# xpoint.net
KiCad netlist of a schematic drawn in Altium Designer
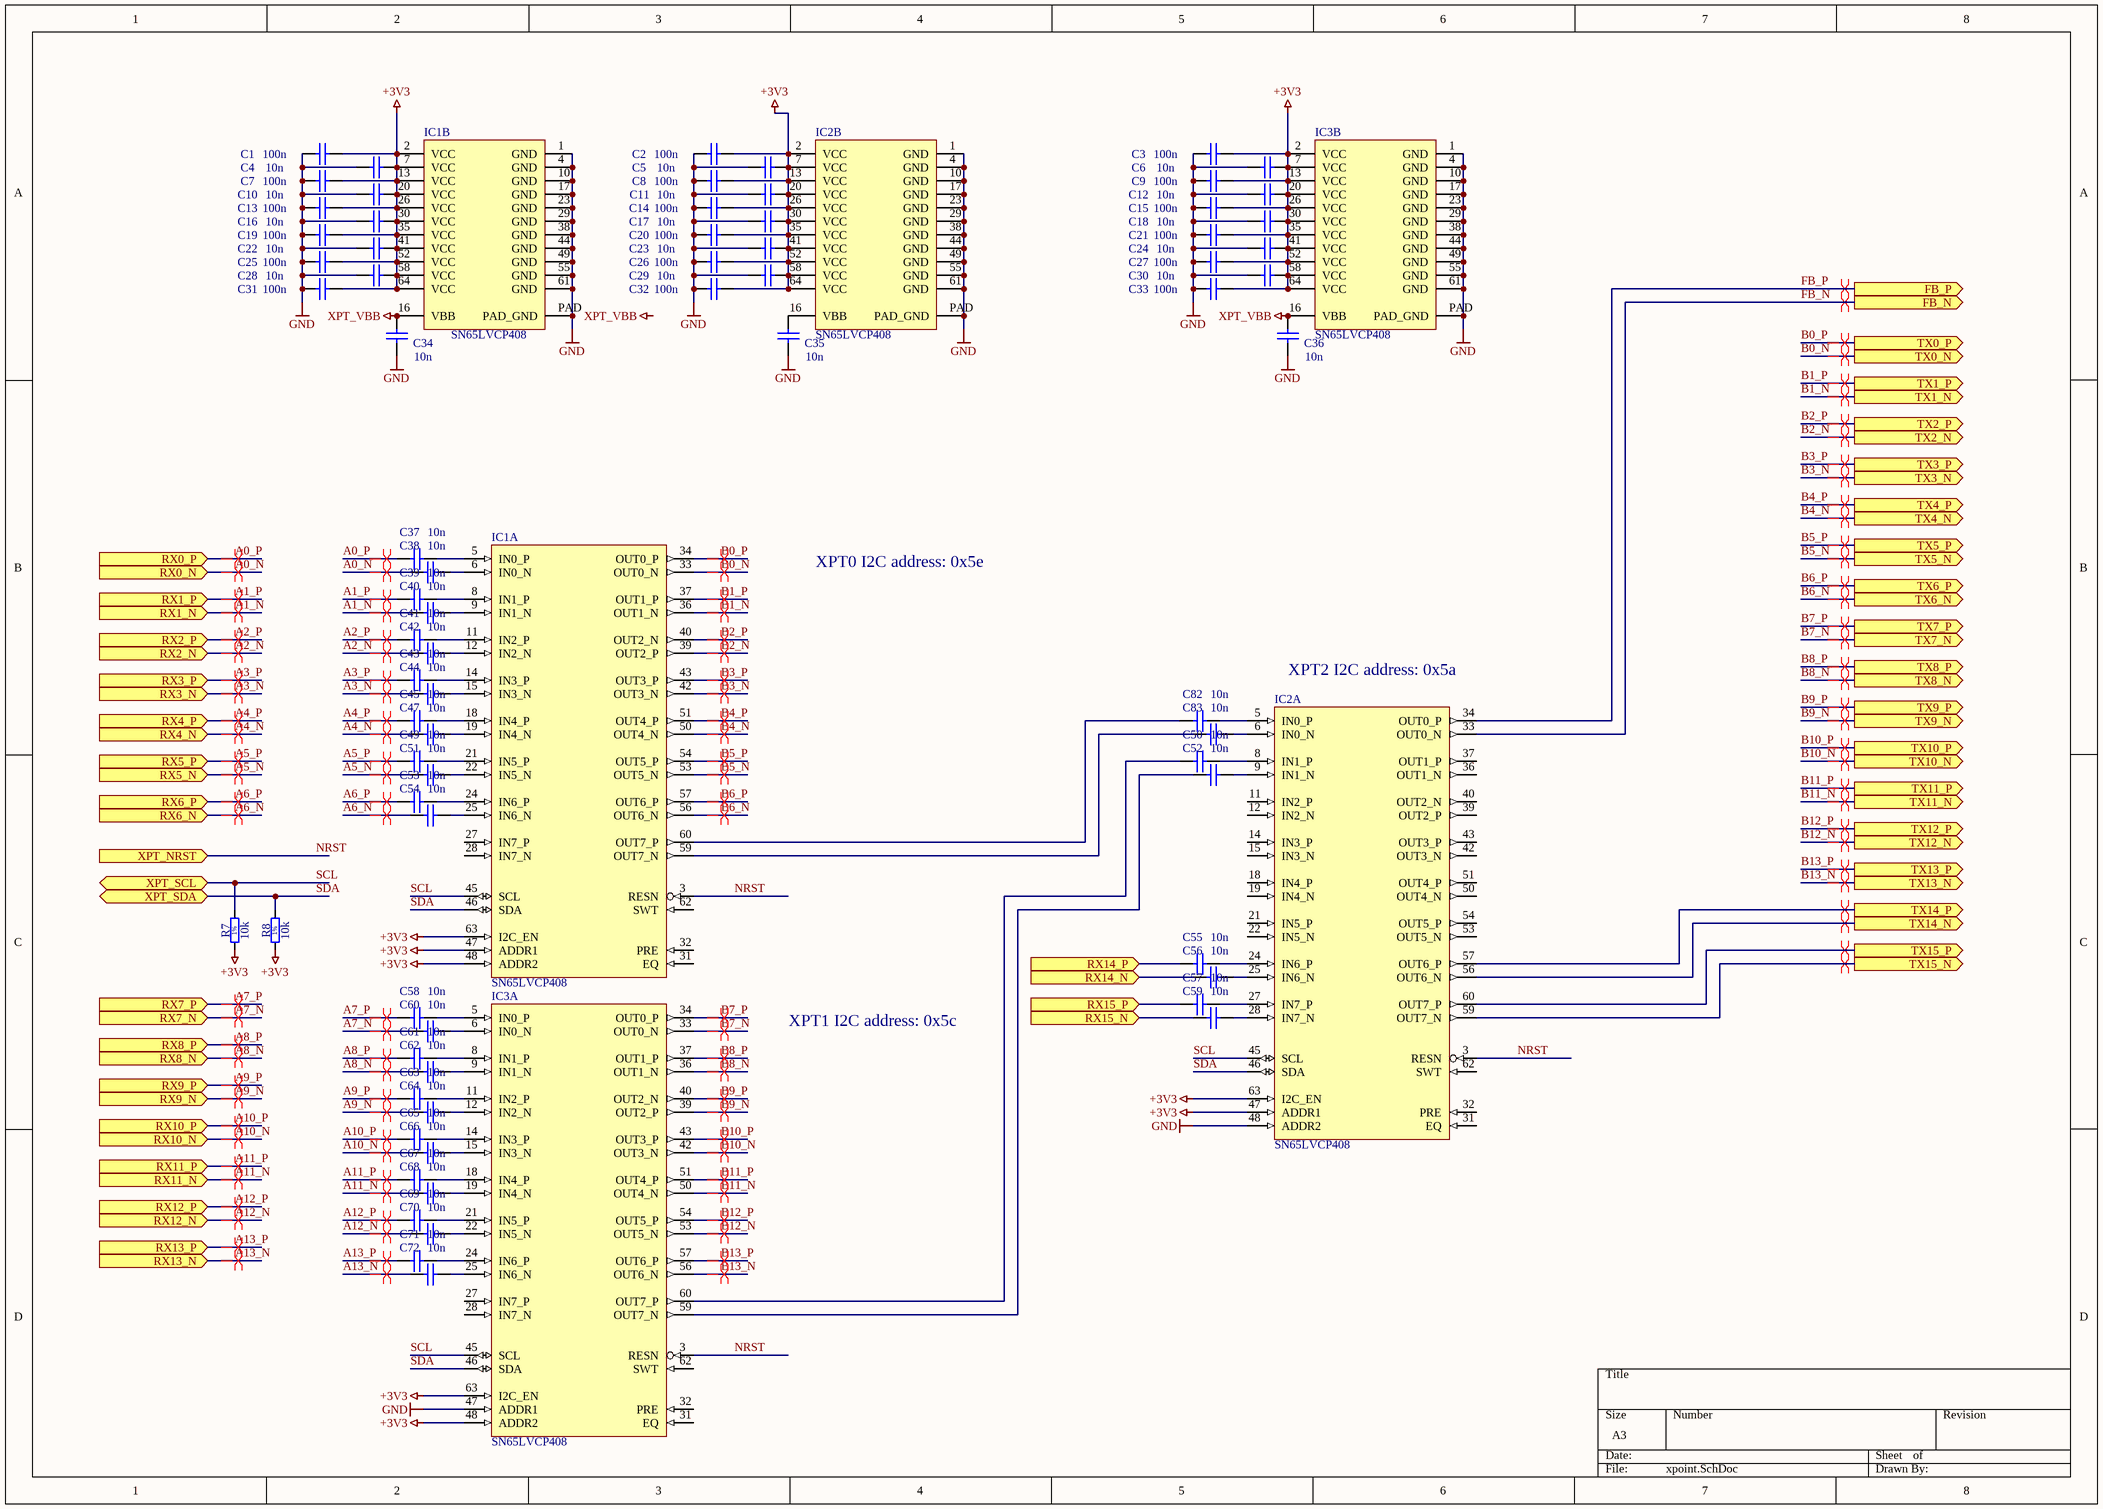
[diagram p0: xpoint.SchDoc]

(export (version "E")
  (design (tool "Eeschema 10.0.6"))
  (components
    (comp (ref "C1")
      (value "100n")
      (footprint "CAPC1608X87N")
      (description "Non-polarised capacitor")
      (fields
        (field (name "PART NUMBER") "CC0603_100NF_50V_10%_X7R")
        (field (name "VOLTAGE") "50V")
        (field (name "AUTHOR") "CERN DEM JLC")
      )
      (libsource (lib "Capacitors") (part "Capacitor - non polarized"))
    )
    (comp (ref "C2")
      (value "100n")
      (footprint "CAPC1608X87N")
      (description "Non-polarised capacitor")
      (fields
        (field (name "PART NUMBER") "CC0603_100NF_50V_10%_X7R")
        (field (name "VOLTAGE") "50V")
        (field (name "AUTHOR") "CERN DEM JLC")
      )
      (libsource (lib "Capacitors") (part "Capacitor - non polarized"))
    )
    (comp (ref "C3")
      (value "100n")
      (footprint "CAPC1608X87N")
      (description "Non-polarised capacitor")
      (fields
        (field (name "PART NUMBER") "CC0603_100NF_50V_10%_X7R")
        (field (name "VOLTAGE") "50V")
        (field (name "AUTHOR") "CERN DEM JLC")
      )
      (libsource (lib "Capacitors") (part "Capacitor - non polarized"))
    )
    (comp (ref "C4")
      (value "10n")
      (footprint "CAPC1608X87N")
      (description "Non-polarised capacitor")
      (fields
        (field (name "PART NUMBER") "CC0603_10NF_50V_10%_X7R")
        (field (name "VOLTAGE") "50V")
        (field (name "AUTHOR") "CERN DEM JLC")
      )
      (libsource (lib "Capacitors") (part "Capacitor - non polarized"))
    )
    (comp (ref "C5")
      (value "10n")
      (footprint "CAPC1608X87N")
      (description "Non-polarised capacitor")
      (fields
        (field (name "PART NUMBER") "CC0603_10NF_50V_10%_X7R")
        (field (name "VOLTAGE") "50V")
        (field (name "AUTHOR") "CERN DEM JLC")
      )
      (libsource (lib "Capacitors") (part "Capacitor - non polarized"))
    )
    (comp (ref "C6")
      (value "10n")
      (footprint "CAPC1608X87N")
      (description "Non-polarised capacitor")
      (fields
        (field (name "PART NUMBER") "CC0603_10NF_50V_10%_X7R")
        (field (name "VOLTAGE") "50V")
        (field (name "AUTHOR") "CERN DEM JLC")
      )
      (libsource (lib "Capacitors") (part "Capacitor - non polarized"))
    )
    (comp (ref "C7")
      (value "100n")
      (footprint "CAPC1608X87N")
      (description "Non-polarised capacitor")
      (fields
        (field (name "PART NUMBER") "CC0603_100NF_50V_10%_X7R")
        (field (name "VOLTAGE") "50V")
        (field (name "AUTHOR") "CERN DEM JLC")
      )
      (libsource (lib "Capacitors") (part "Capacitor - non polarized"))
    )
    (comp (ref "C8")
      (value "100n")
      (footprint "CAPC1608X87N")
      (description "Non-polarised capacitor")
      (fields
        (field (name "PART NUMBER") "CC0603_100NF_50V_10%_X7R")
        (field (name "VOLTAGE") "50V")
        (field (name "AUTHOR") "CERN DEM JLC")
      )
      (libsource (lib "Capacitors") (part "Capacitor - non polarized"))
    )
    (comp (ref "C9")
      (value "100n")
      (footprint "CAPC1608X87N")
      (description "Non-polarised capacitor")
      (fields
        (field (name "PART NUMBER") "CC0603_100NF_50V_10%_X7R")
        (field (name "VOLTAGE") "50V")
        (field (name "AUTHOR") "CERN DEM JLC")
      )
      (libsource (lib "Capacitors") (part "Capacitor - non polarized"))
    )
    (comp (ref "C10")
      (value "10n")
      (footprint "CAPC1608X87N")
      (description "Non-polarised capacitor")
      (fields
        (field (name "PART NUMBER") "CC0603_10NF_50V_10%_X7R")
        (field (name "VOLTAGE") "50V")
        (field (name "AUTHOR") "CERN DEM JLC")
      )
      (libsource (lib "Capacitors") (part "Capacitor - non polarized"))
    )
    (comp (ref "C11")
      (value "10n")
      (footprint "CAPC1608X87N")
      (description "Non-polarised capacitor")
      (fields
        (field (name "PART NUMBER") "CC0603_10NF_50V_10%_X7R")
        (field (name "VOLTAGE") "50V")
        (field (name "AUTHOR") "CERN DEM JLC")
      )
      (libsource (lib "Capacitors") (part "Capacitor - non polarized"))
    )
    (comp (ref "C12")
      (value "10n")
      (footprint "CAPC1608X87N")
      (description "Non-polarised capacitor")
      (fields
        (field (name "PART NUMBER") "CC0603_10NF_50V_10%_X7R")
        (field (name "VOLTAGE") "50V")
        (field (name "AUTHOR") "CERN DEM JLC")
      )
      (libsource (lib "Capacitors") (part "Capacitor - non polarized"))
    )
    (comp (ref "C13")
      (value "100n")
      (footprint "CAPC1608X87N")
      (description "Non-polarised capacitor")
      (fields
        (field (name "PART NUMBER") "CC0603_100NF_50V_10%_X7R")
        (field (name "VOLTAGE") "50V")
        (field (name "AUTHOR") "CERN DEM JLC")
      )
      (libsource (lib "Capacitors") (part "Capacitor - non polarized"))
    )
    (comp (ref "C14")
      (value "100n")
      (footprint "CAPC1608X87N")
      (description "Non-polarised capacitor")
      (fields
        (field (name "PART NUMBER") "CC0603_100NF_50V_10%_X7R")
        (field (name "VOLTAGE") "50V")
        (field (name "AUTHOR") "CERN DEM JLC")
      )
      (libsource (lib "Capacitors") (part "Capacitor - non polarized"))
    )
    (comp (ref "C15")
      (value "100n")
      (footprint "CAPC1608X87N")
      (description "Non-polarised capacitor")
      (fields
        (field (name "PART NUMBER") "CC0603_100NF_50V_10%_X7R")
        (field (name "VOLTAGE") "50V")
        (field (name "AUTHOR") "CERN DEM JLC")
      )
      (libsource (lib "Capacitors") (part "Capacitor - non polarized"))
    )
    (comp (ref "C16")
      (value "10n")
      (footprint "CAPC1608X87N")
      (description "Non-polarised capacitor")
      (fields
        (field (name "PART NUMBER") "CC0603_10NF_50V_10%_X7R")
        (field (name "VOLTAGE") "50V")
        (field (name "AUTHOR") "CERN DEM JLC")
      )
      (libsource (lib "Capacitors") (part "Capacitor - non polarized"))
    )
    (comp (ref "C17")
      (value "10n")
      (footprint "CAPC1608X87N")
      (description "Non-polarised capacitor")
      (fields
        (field (name "PART NUMBER") "CC0603_10NF_50V_10%_X7R")
        (field (name "VOLTAGE") "50V")
        (field (name "AUTHOR") "CERN DEM JLC")
      )
      (libsource (lib "Capacitors") (part "Capacitor - non polarized"))
    )
    (comp (ref "C18")
      (value "10n")
      (footprint "CAPC1608X87N")
      (description "Non-polarised capacitor")
      (fields
        (field (name "PART NUMBER") "CC0603_10NF_50V_10%_X7R")
        (field (name "VOLTAGE") "50V")
        (field (name "AUTHOR") "CERN DEM JLC")
      )
      (libsource (lib "Capacitors") (part "Capacitor - non polarized"))
    )
    (comp (ref "C19")
      (value "100n")
      (footprint "CAPC1608X87N")
      (description "Non-polarised capacitor")
      (fields
        (field (name "PART NUMBER") "CC0603_100NF_50V_10%_X7R")
        (field (name "VOLTAGE") "50V")
        (field (name "AUTHOR") "CERN DEM JLC")
      )
      (libsource (lib "Capacitors") (part "Capacitor - non polarized"))
    )
    (comp (ref "C20")
      (value "100n")
      (footprint "CAPC1608X87N")
      (description "Non-polarised capacitor")
      (fields
        (field (name "PART NUMBER") "CC0603_100NF_50V_10%_X7R")
        (field (name "VOLTAGE") "50V")
        (field (name "AUTHOR") "CERN DEM JLC")
      )
      (libsource (lib "Capacitors") (part "Capacitor - non polarized"))
    )
    (comp (ref "C21")
      (value "100n")
      (footprint "CAPC1608X87N")
      (description "Non-polarised capacitor")
      (fields
        (field (name "PART NUMBER") "CC0603_100NF_50V_10%_X7R")
        (field (name "VOLTAGE") "50V")
        (field (name "AUTHOR") "CERN DEM JLC")
      )
      (libsource (lib "Capacitors") (part "Capacitor - non polarized"))
    )
    (comp (ref "C22")
      (value "10n")
      (footprint "CAPC1608X87N")
      (description "Non-polarised capacitor")
      (fields
        (field (name "PART NUMBER") "CC0603_10NF_50V_10%_X7R")
        (field (name "VOLTAGE") "50V")
        (field (name "AUTHOR") "CERN DEM JLC")
      )
      (libsource (lib "Capacitors") (part "Capacitor - non polarized"))
    )
    (comp (ref "C23")
      (value "10n")
      (footprint "CAPC1608X87N")
      (description "Non-polarised capacitor")
      (fields
        (field (name "PART NUMBER") "CC0603_10NF_50V_10%_X7R")
        (field (name "VOLTAGE") "50V")
        (field (name "AUTHOR") "CERN DEM JLC")
      )
      (libsource (lib "Capacitors") (part "Capacitor - non polarized"))
    )
    (comp (ref "C24")
      (value "10n")
      (footprint "CAPC1608X87N")
      (description "Non-polarised capacitor")
      (fields
        (field (name "PART NUMBER") "CC0603_10NF_50V_10%_X7R")
        (field (name "VOLTAGE") "50V")
        (field (name "AUTHOR") "CERN DEM JLC")
      )
      (libsource (lib "Capacitors") (part "Capacitor - non polarized"))
    )
    (comp (ref "C25")
      (value "100n")
      (footprint "CAPC1608X87N")
      (description "Non-polarised capacitor")
      (fields
        (field (name "PART NUMBER") "CC0603_100NF_50V_10%_X7R")
        (field (name "VOLTAGE") "50V")
        (field (name "AUTHOR") "CERN DEM JLC")
      )
      (libsource (lib "Capacitors") (part "Capacitor - non polarized"))
    )
    (comp (ref "C26")
      (value "100n")
      (footprint "CAPC1608X87N")
      (description "Non-polarised capacitor")
      (fields
        (field (name "PART NUMBER") "CC0603_100NF_50V_10%_X7R")
        (field (name "VOLTAGE") "50V")
        (field (name "AUTHOR") "CERN DEM JLC")
      )
      (libsource (lib "Capacitors") (part "Capacitor - non polarized"))
    )
    (comp (ref "C27")
      (value "100n")
      (footprint "CAPC1608X87N")
      (description "Non-polarised capacitor")
      (fields
        (field (name "PART NUMBER") "CC0603_100NF_50V_10%_X7R")
        (field (name "VOLTAGE") "50V")
        (field (name "AUTHOR") "CERN DEM JLC")
      )
      (libsource (lib "Capacitors") (part "Capacitor - non polarized"))
    )
    (comp (ref "C28")
      (value "10n")
      (footprint "CAPC1608X87N")
      (description "Non-polarised capacitor")
      (fields
        (field (name "PART NUMBER") "CC0603_10NF_50V_10%_X7R")
        (field (name "VOLTAGE") "50V")
        (field (name "AUTHOR") "CERN DEM JLC")
      )
      (libsource (lib "Capacitors") (part "Capacitor - non polarized"))
    )
    (comp (ref "C29")
      (value "10n")
      (footprint "CAPC1608X87N")
      (description "Non-polarised capacitor")
      (fields
        (field (name "PART NUMBER") "CC0603_10NF_50V_10%_X7R")
        (field (name "VOLTAGE") "50V")
        (field (name "AUTHOR") "CERN DEM JLC")
      )
      (libsource (lib "Capacitors") (part "Capacitor - non polarized"))
    )
    (comp (ref "C30")
      (value "10n")
      (footprint "CAPC1608X87N")
      (description "Non-polarised capacitor")
      (fields
        (field (name "PART NUMBER") "CC0603_10NF_50V_10%_X7R")
        (field (name "VOLTAGE") "50V")
        (field (name "AUTHOR") "CERN DEM JLC")
      )
      (libsource (lib "Capacitors") (part "Capacitor - non polarized"))
    )
    (comp (ref "C31")
      (value "100n")
      (footprint "CAPC1608X87N")
      (description "Non-polarised capacitor")
      (fields
        (field (name "PART NUMBER") "CC0603_100NF_50V_10%_X7R")
        (field (name "VOLTAGE") "50V")
        (field (name "AUTHOR") "CERN DEM JLC")
      )
      (libsource (lib "Capacitors") (part "Capacitor - non polarized"))
    )
    (comp (ref "C32")
      (value "100n")
      (footprint "CAPC1608X87N")
      (description "Non-polarised capacitor")
      (fields
        (field (name "PART NUMBER") "CC0603_100NF_50V_10%_X7R")
        (field (name "VOLTAGE") "50V")
        (field (name "AUTHOR") "CERN DEM JLC")
      )
      (libsource (lib "Capacitors") (part "Capacitor - non polarized"))
    )
    (comp (ref "C33")
      (value "100n")
      (footprint "CAPC1608X87N")
      (description "Non-polarised capacitor")
      (fields
        (field (name "PART NUMBER") "CC0603_100NF_50V_10%_X7R")
        (field (name "VOLTAGE") "50V")
        (field (name "AUTHOR") "CERN DEM JLC")
      )
      (libsource (lib "Capacitors") (part "Capacitor - non polarized"))
    )
    (comp (ref "C34")
      (value "10n")
      (footprint "CAPC1608X87N")
      (description "Non-polarised capacitor")
      (fields
        (field (name "PART NUMBER") "CC0603_10NF_50V_10%_X7R")
        (field (name "VOLTAGE") "50V")
        (field (name "AUTHOR") "CERN DEM JLC")
      )
      (libsource (lib "Capacitors") (part "Capacitor - non polarized"))
    )
    (comp (ref "C35")
      (value "10n")
      (footprint "CAPC1608X87N")
      (description "Non-polarised capacitor")
      (fields
        (field (name "PART NUMBER") "CC0603_10NF_50V_10%_X7R")
        (field (name "VOLTAGE") "50V")
        (field (name "AUTHOR") "CERN DEM JLC")
      )
      (libsource (lib "Capacitors") (part "Capacitor - non polarized"))
    )
    (comp (ref "C36")
      (value "10n")
      (footprint "CAPC1608X87N")
      (description "Non-polarised capacitor")
      (fields
        (field (name "PART NUMBER") "CC0603_10NF_50V_10%_X7R")
        (field (name "VOLTAGE") "50V")
        (field (name "AUTHOR") "CERN DEM JLC")
      )
      (libsource (lib "Capacitors") (part "Capacitor - non polarized"))
    )
    (comp (ref "C37")
      (value "10n")
      (footprint "CAPC1608X87N")
      (description "Non-polarised capacitor")
      (fields
        (field (name "PART NUMBER") "CC0603_10NF_50V_10%_X7R")
        (field (name "VOLTAGE") "50V")
        (field (name "AUTHOR") "CERN DEM JLC")
      )
      (libsource (lib "Capacitors") (part "Capacitor - non polarized"))
    )
    (comp (ref "C38")
      (value "10n")
      (footprint "CAPC1608X87N")
      (description "Non-polarised capacitor")
      (fields
        (field (name "PART NUMBER") "CC0603_10NF_50V_10%_X7R")
        (field (name "VOLTAGE") "50V")
        (field (name "AUTHOR") "CERN DEM JLC")
      )
      (libsource (lib "Capacitors") (part "Capacitor - non polarized"))
    )
    (comp (ref "C39")
      (value "10n")
      (footprint "CAPC1608X87N")
      (description "Non-polarised capacitor")
      (fields
        (field (name "PART NUMBER") "CC0603_10NF_50V_10%_X7R")
        (field (name "VOLTAGE") "50V")
        (field (name "AUTHOR") "CERN DEM JLC")
      )
      (libsource (lib "Capacitors") (part "Capacitor - non polarized"))
    )
    (comp (ref "C40")
      (value "10n")
      (footprint "CAPC1608X87N")
      (description "Non-polarised capacitor")
      (fields
        (field (name "PART NUMBER") "CC0603_10NF_50V_10%_X7R")
        (field (name "VOLTAGE") "50V")
        (field (name "AUTHOR") "CERN DEM JLC")
      )
      (libsource (lib "Capacitors") (part "Capacitor - non polarized"))
    )
    (comp (ref "C41")
      (value "10n")
      (footprint "CAPC1608X87N")
      (description "Non-polarised capacitor")
      (fields
        (field (name "PART NUMBER") "CC0603_10NF_50V_10%_X7R")
        (field (name "VOLTAGE") "50V")
        (field (name "AUTHOR") "CERN DEM JLC")
      )
      (libsource (lib "Capacitors") (part "Capacitor - non polarized"))
    )
    (comp (ref "C42")
      (value "10n")
      (footprint "CAPC1608X87N")
      (description "Non-polarised capacitor")
      (fields
        (field (name "PART NUMBER") "CC0603_10NF_50V_10%_X7R")
        (field (name "VOLTAGE") "50V")
        (field (name "AUTHOR") "CERN DEM JLC")
      )
      (libsource (lib "Capacitors") (part "Capacitor - non polarized"))
    )
    (comp (ref "C43")
      (value "10n")
      (footprint "CAPC1608X87N")
      (description "Non-polarised capacitor")
      (fields
        (field (name "PART NUMBER") "CC0603_10NF_50V_10%_X7R")
        (field (name "VOLTAGE") "50V")
        (field (name "AUTHOR") "CERN DEM JLC")
      )
      (libsource (lib "Capacitors") (part "Capacitor - non polarized"))
    )
    (comp (ref "C44")
      (value "10n")
      (footprint "CAPC1608X87N")
      (description "Non-polarised capacitor")
      (fields
        (field (name "PART NUMBER") "CC0603_10NF_50V_10%_X7R")
        (field (name "VOLTAGE") "50V")
        (field (name "AUTHOR") "CERN DEM JLC")
      )
      (libsource (lib "Capacitors") (part "Capacitor - non polarized"))
    )
    (comp (ref "C45")
      (value "10n")
      (footprint "CAPC1608X87N")
      (description "Non-polarised capacitor")
      (fields
        (field (name "PART NUMBER") "CC0603_10NF_50V_10%_X7R")
        (field (name "VOLTAGE") "50V")
        (field (name "AUTHOR") "CERN DEM JLC")
      )
      (libsource (lib "Capacitors") (part "Capacitor - non polarized"))
    )
    (comp (ref "C47")
      (value "10n")
      (footprint "CAPC1608X87N")
      (description "Non-polarised capacitor")
      (fields
        (field (name "PART NUMBER") "CC0603_10NF_50V_10%_X7R")
        (field (name "VOLTAGE") "50V")
        (field (name "AUTHOR") "CERN DEM JLC")
      )
      (libsource (lib "Capacitors") (part "Capacitor - non polarized"))
    )
    (comp (ref "C49")
      (value "10n")
      (footprint "CAPC1608X87N")
      (description "Non-polarised capacitor")
      (fields
        (field (name "PART NUMBER") "CC0603_10NF_50V_10%_X7R")
        (field (name "VOLTAGE") "50V")
        (field (name "AUTHOR") "CERN DEM JLC")
      )
      (libsource (lib "Capacitors") (part "Capacitor - non polarized"))
    )
    (comp (ref "C50")
      (value "10n")
      (footprint "CAPC1608X87N")
      (description "Non-polarised capacitor")
      (fields
        (field (name "PART NUMBER") "CC0603_10NF_50V_10%_X7R")
        (field (name "VOLTAGE") "50V")
        (field (name "AUTHOR") "CERN DEM JLC")
      )
      (libsource (lib "Capacitors") (part "Capacitor - non polarized"))
    )
    (comp (ref "C51")
      (value "10n")
      (footprint "CAPC1608X87N")
      (description "Non-polarised capacitor")
      (fields
        (field (name "PART NUMBER") "CC0603_10NF_50V_10%_X7R")
        (field (name "VOLTAGE") "50V")
        (field (name "AUTHOR") "CERN DEM JLC")
      )
      (libsource (lib "Capacitors") (part "Capacitor - non polarized"))
    )
    (comp (ref "C52")
      (value "10n")
      (footprint "CAPC1608X87N")
      (description "Non-polarised capacitor")
      (fields
        (field (name "PART NUMBER") "CC0603_10NF_50V_10%_X7R")
        (field (name "VOLTAGE") "50V")
        (field (name "AUTHOR") "CERN DEM JLC")
      )
      (libsource (lib "Capacitors") (part "Capacitor - non polarized"))
    )
    (comp (ref "C53")
      (value "10n")
      (footprint "CAPC1608X87N")
      (description "Non-polarised capacitor")
      (fields
        (field (name "PART NUMBER") "CC0603_10NF_50V_10%_X7R")
        (field (name "VOLTAGE") "50V")
        (field (name "AUTHOR") "CERN DEM JLC")
      )
      (libsource (lib "Capacitors") (part "Capacitor - non polarized"))
    )
    (comp (ref "C54")
      (value "10n")
      (footprint "CAPC1608X87N")
      (description "Non-polarised capacitor")
      (fields
        (field (name "PART NUMBER") "CC0603_10NF_50V_10%_X7R")
        (field (name "VOLTAGE") "50V")
        (field (name "AUTHOR") "CERN DEM JLC")
      )
      (libsource (lib "Capacitors") (part "Capacitor - non polarized"))
    )
    (comp (ref "C55")
      (value "10n")
      (footprint "CAPC1608X87N")
      (description "Non-polarised capacitor")
      (fields
        (field (name "PART NUMBER") "CC0603_10NF_50V_10%_X7R")
        (field (name "VOLTAGE") "50V")
        (field (name "AUTHOR") "CERN DEM JLC")
      )
      (libsource (lib "Capacitors") (part "Capacitor - non polarized"))
    )
    (comp (ref "C56")
      (value "10n")
      (footprint "CAPC1608X87N")
      (description "Non-polarised capacitor")
      (fields
        (field (name "PART NUMBER") "CC0603_10NF_50V_10%_X7R")
        (field (name "VOLTAGE") "50V")
        (field (name "AUTHOR") "CERN DEM JLC")
      )
      (libsource (lib "Capacitors") (part "Capacitor - non polarized"))
    )
    (comp (ref "C57")
      (value "10n")
      (footprint "CAPC1608X87N")
      (description "Non-polarised capacitor")
      (fields
        (field (name "PART NUMBER") "CC0603_10NF_50V_10%_X7R")
        (field (name "VOLTAGE") "50V")
        (field (name "AUTHOR") "CERN DEM JLC")
      )
      (libsource (lib "Capacitors") (part "Capacitor - non polarized"))
    )
    (comp (ref "C58")
      (value "10n")
      (footprint "CAPC1608X87N")
      (description "Non-polarised capacitor")
      (fields
        (field (name "PART NUMBER") "CC0603_10NF_50V_10%_X7R")
        (field (name "VOLTAGE") "50V")
        (field (name "AUTHOR") "CERN DEM JLC")
      )
      (libsource (lib "Capacitors") (part "Capacitor - non polarized"))
    )
    (comp (ref "C59")
      (value "10n")
      (footprint "CAPC1608X87N")
      (description "Non-polarised capacitor")
      (fields
        (field (name "PART NUMBER") "CC0603_10NF_50V_10%_X7R")
        (field (name "VOLTAGE") "50V")
        (field (name "AUTHOR") "CERN DEM JLC")
      )
      (libsource (lib "Capacitors") (part "Capacitor - non polarized"))
    )
    (comp (ref "C60")
      (value "10n")
      (footprint "CAPC1608X87N")
      (description "Non-polarised capacitor")
      (fields
        (field (name "PART NUMBER") "CC0603_10NF_50V_10%_X7R")
        (field (name "VOLTAGE") "50V")
        (field (name "AUTHOR") "CERN DEM JLC")
      )
      (libsource (lib "Capacitors") (part "Capacitor - non polarized"))
    )
    (comp (ref "C61")
      (value "10n")
      (footprint "CAPC1608X87N")
      (description "Non-polarised capacitor")
      (fields
        (field (name "PART NUMBER") "CC0603_10NF_50V_10%_X7R")
        (field (name "VOLTAGE") "50V")
        (field (name "AUTHOR") "CERN DEM JLC")
      )
      (libsource (lib "Capacitors") (part "Capacitor - non polarized"))
    )
    (comp (ref "C62")
      (value "10n")
      (footprint "CAPC1608X87N")
      (description "Non-polarised capacitor")
      (fields
        (field (name "PART NUMBER") "CC0603_10NF_50V_10%_X7R")
        (field (name "VOLTAGE") "50V")
        (field (name "AUTHOR") "CERN DEM JLC")
      )
      (libsource (lib "Capacitors") (part "Capacitor - non polarized"))
    )
    (comp (ref "C63")
      (value "10n")
      (footprint "CAPC1608X87N")
      (description "Non-polarised capacitor")
      (fields
        (field (name "PART NUMBER") "CC0603_10NF_50V_10%_X7R")
        (field (name "VOLTAGE") "50V")
        (field (name "AUTHOR") "CERN DEM JLC")
      )
      (libsource (lib "Capacitors") (part "Capacitor - non polarized"))
    )
    (comp (ref "C64")
      (value "10n")
      (footprint "CAPC1608X87N")
      (description "Non-polarised capacitor")
      (fields
        (field (name "PART NUMBER") "CC0603_10NF_50V_10%_X7R")
        (field (name "VOLTAGE") "50V")
        (field (name "AUTHOR") "CERN DEM JLC")
      )
      (libsource (lib "Capacitors") (part "Capacitor - non polarized"))
    )
    (comp (ref "C65")
      (value "10n")
      (footprint "CAPC1608X87N")
      (description "Non-polarised capacitor")
      (fields
        (field (name "PART NUMBER") "CC0603_10NF_50V_10%_X7R")
        (field (name "VOLTAGE") "50V")
        (field (name "AUTHOR") "CERN DEM JLC")
      )
      (libsource (lib "Capacitors") (part "Capacitor - non polarized"))
    )
    (comp (ref "C66")
      (value "10n")
      (footprint "CAPC1608X87N")
      (description "Non-polarised capacitor")
      (fields
        (field (name "PART NUMBER") "CC0603_10NF_50V_10%_X7R")
        (field (name "VOLTAGE") "50V")
        (field (name "AUTHOR") "CERN DEM JLC")
      )
      (libsource (lib "Capacitors") (part "Capacitor - non polarized"))
    )
    (comp (ref "C67")
      (value "10n")
      (footprint "CAPC1608X87N")
      (description "Non-polarised capacitor")
      (fields
        (field (name "PART NUMBER") "CC0603_10NF_50V_10%_X7R")
        (field (name "VOLTAGE") "50V")
        (field (name "AUTHOR") "CERN DEM JLC")
      )
      (libsource (lib "Capacitors") (part "Capacitor - non polarized"))
    )
    (comp (ref "C68")
      (value "10n")
      (footprint "CAPC1608X87N")
      (description "Non-polarised capacitor")
      (fields
        (field (name "PART NUMBER") "CC0603_10NF_50V_10%_X7R")
        (field (name "VOLTAGE") "50V")
        (field (name "AUTHOR") "CERN DEM JLC")
      )
      (libsource (lib "Capacitors") (part "Capacitor - non polarized"))
    )
    (comp (ref "C69")
      (value "10n")
      (footprint "CAPC1608X87N")
      (description "Non-polarised capacitor")
      (fields
        (field (name "PART NUMBER") "CC0603_10NF_50V_10%_X7R")
        (field (name "VOLTAGE") "50V")
        (field (name "AUTHOR") "CERN DEM JLC")
      )
      (libsource (lib "Capacitors") (part "Capacitor - non polarized"))
    )
    (comp (ref "C70")
      (value "10n")
      (footprint "CAPC1608X87N")
      (description "Non-polarised capacitor")
      (fields
        (field (name "PART NUMBER") "CC0603_10NF_50V_10%_X7R")
        (field (name "VOLTAGE") "50V")
        (field (name "AUTHOR") "CERN DEM JLC")
      )
      (libsource (lib "Capacitors") (part "Capacitor - non polarized"))
    )
    (comp (ref "C71")
      (value "10n")
      (footprint "CAPC1608X87N")
      (description "Non-polarised capacitor")
      (fields
        (field (name "PART NUMBER") "CC0603_10NF_50V_10%_X7R")
        (field (name "VOLTAGE") "50V")
        (field (name "AUTHOR") "CERN DEM JLC")
      )
      (libsource (lib "Capacitors") (part "Capacitor - non polarized"))
    )
    (comp (ref "C72")
      (value "10n")
      (footprint "CAPC1608X87N")
      (description "Non-polarised capacitor")
      (fields
        (field (name "PART NUMBER") "CC0603_10NF_50V_10%_X7R")
        (field (name "VOLTAGE") "50V")
        (field (name "AUTHOR") "CERN DEM JLC")
      )
      (libsource (lib "Capacitors") (part "Capacitor - non polarized"))
    )
    (comp (ref "C82")
      (value "10n")
      (footprint "CAPC1608X87N")
      (description "Non-polarised capacitor")
      (fields
        (field (name "PART NUMBER") "CC0603_10NF_50V_10%_X7R")
        (field (name "VOLTAGE") "50V")
        (field (name "AUTHOR") "CERN DEM JLC")
      )
      (libsource (lib "Capacitors") (part "Capacitor - non polarized"))
    )
    (comp (ref "C83")
      (value "10n")
      (footprint "CAPC1608X87N")
      (description "Non-polarised capacitor")
      (fields
        (field (name "PART NUMBER") "CC0603_10NF_50V_10%_X7R")
        (field (name "VOLTAGE") "50V")
        (field (name "AUTHOR") "CERN DEM JLC")
      )
      (libsource (lib "Capacitors") (part "Capacitor - non polarized"))
    )
    (comp (ref "IC1")
      (value "SN65LVCP408")
      (footprint "HTQFP64")
      (description "TI 8x8 gigabit crosspoint")
      (libsource (lib "wr_switch") (part "SN65LVCP408"))
    )
    (comp (ref "IC2")
      (value "SN65LVCP408")
      (footprint "HTQFP64")
      (description "TI 8x8 gigabit crosspoint")
      (libsource (lib "wr_switch") (part "SN65LVCP408"))
    )
    (comp (ref "IC3")
      (value "SN65LVCP408")
      (footprint "HTQFP64")
      (description "TI 8x8 gigabit crosspoint")
      (libsource (lib "wr_switch") (part "SN65LVCP408"))
    )
    (comp (ref "R7")
      (value "10k")
      (footprint "RESC1608X55N")
      (description "Resistor - 1%")
      (fields
        (field (name "PART NUMBER") "R0603_10K_1%_0.1W_100PPM")
        (field (name "POWER") "0.1W")
        (field (name "AUTHOR") "CERN DEM JLC")
      )
      (libsource (lib "Resistors") (part "Resistor - 1%"))
    )
    (comp (ref "R8")
      (value "10k")
      (footprint "RESC1608X55N")
      (description "Resistor - 1%")
      (fields
        (field (name "PART NUMBER") "R0603_10K_1%_0.1W_100PPM")
        (field (name "POWER") "0.1W")
        (field (name "AUTHOR") "CERN DEM JLC")
      )
      (libsource (lib "Resistors") (part "Resistor - 1%"))
    )
  )
  (nets
    (net (code "1") (name "+3V3") (class "Default")
      (node (ref "C1") (pin "2") (pinfunction "2_2") (pintype "passive"))
      (node (ref "C10") (pin "2") (pinfunction "2_2") (pintype "passive"))
      (node (ref "C11") (pin "2") (pinfunction "2_2") (pintype "passive"))
      (node (ref "C12") (pin "2") (pinfunction "2_2") (pintype "passive"))
      (node (ref "C13") (pin "2") (pinfunction "2_2") (pintype "passive"))
      (node (ref "C14") (pin "2") (pinfunction "2_2") (pintype "passive"))
      (node (ref "C15") (pin "2") (pinfunction "2_2") (pintype "passive"))
      (node (ref "C16") (pin "2") (pinfunction "2_2") (pintype "passive"))
      (node (ref "C17") (pin "2") (pinfunction "2_2") (pintype "passive"))
      (node (ref "C18") (pin "2") (pinfunction "2_2") (pintype "passive"))
      (node (ref "C19") (pin "2") (pinfunction "2_2") (pintype "passive"))
      (node (ref "C2") (pin "2") (pinfunction "2_2") (pintype "passive"))
      (node (ref "C20") (pin "2") (pinfunction "2_2") (pintype "passive"))
      (node (ref "C21") (pin "2") (pinfunction "2_2") (pintype "passive"))
      (node (ref "C22") (pin "2") (pinfunction "2_2") (pintype "passive"))
      (node (ref "C23") (pin "2") (pinfunction "2_2") (pintype "passive"))
      (node (ref "C24") (pin "2") (pinfunction "2_2") (pintype "passive"))
      (node (ref "C25") (pin "2") (pinfunction "2_2") (pintype "passive"))
      (node (ref "C26") (pin "2") (pinfunction "2_2") (pintype "passive"))
      (node (ref "C27") (pin "2") (pinfunction "2_2") (pintype "passive"))
      (node (ref "C28") (pin "2") (pinfunction "2_2") (pintype "passive"))
      (node (ref "C29") (pin "2") (pinfunction "2_2") (pintype "passive"))
      (node (ref "C3") (pin "2") (pinfunction "2_2") (pintype "passive"))
      (node (ref "C30") (pin "2") (pinfunction "2_2") (pintype "passive"))
      (node (ref "C31") (pin "2") (pinfunction "2_2") (pintype "passive"))
      (node (ref "C32") (pin "2") (pinfunction "2_2") (pintype "passive"))
      (node (ref "C33") (pin "2") (pinfunction "2_2") (pintype "passive"))
      (node (ref "C4") (pin "2") (pinfunction "2_2") (pintype "passive"))
      (node (ref "C5") (pin "2") (pinfunction "2_2") (pintype "passive"))
      (node (ref "C6") (pin "2") (pinfunction "2_2") (pintype "passive"))
      (node (ref "C7") (pin "2") (pinfunction "2_2") (pintype "passive"))
      (node (ref "C8") (pin "2") (pinfunction "2_2") (pintype "passive"))
      (node (ref "C9") (pin "2") (pinfunction "2_2") (pintype "passive"))
      (node (ref "IC1") (pin "13") (pinfunction "VCC_13") (pintype "power_in"))
      (node (ref "IC1") (pin "2") (pinfunction "VCC_2") (pintype "power_in"))
      (node (ref "IC1") (pin "20") (pinfunction "VCC_20") (pintype "power_in"))
      (node (ref "IC1") (pin "26") (pinfunction "VCC_26") (pintype "power_in"))
      (node (ref "IC1") (pin "30") (pinfunction "VCC_30") (pintype "power_in"))
      (node (ref "IC1") (pin "35") (pinfunction "VCC_35") (pintype "power_in"))
      (node (ref "IC1") (pin "41") (pinfunction "VCC_41") (pintype "power_in"))
      (node (ref "IC1") (pin "47") (pinfunction "ADDR1_47") (pintype "input"))
      (node (ref "IC1") (pin "48") (pinfunction "ADDR2_48") (pintype "input"))
      (node (ref "IC1") (pin "52") (pinfunction "VCC_52") (pintype "power_in"))
      (node (ref "IC1") (pin "58") (pinfunction "VCC_58") (pintype "power_in"))
      (node (ref "IC1") (pin "63") (pinfunction "I2C_EN_63") (pintype "input"))
      (node (ref "IC1") (pin "64") (pinfunction "VCC_64") (pintype "power_in"))
      (node (ref "IC1") (pin "7") (pinfunction "VCC_7") (pintype "power_in"))
      (node (ref "IC2") (pin "13") (pinfunction "VCC_13") (pintype "power_in"))
      (node (ref "IC2") (pin "2") (pinfunction "VCC_2") (pintype "power_in"))
      (node (ref "IC2") (pin "20") (pinfunction "VCC_20") (pintype "power_in"))
      (node (ref "IC2") (pin "26") (pinfunction "VCC_26") (pintype "power_in"))
      (node (ref "IC2") (pin "30") (pinfunction "VCC_30") (pintype "power_in"))
      (node (ref "IC2") (pin "35") (pinfunction "VCC_35") (pintype "power_in"))
      (node (ref "IC2") (pin "41") (pinfunction "VCC_41") (pintype "power_in"))
      (node (ref "IC2") (pin "47") (pinfunction "ADDR1_47") (pintype "input"))
      (node (ref "IC2") (pin "52") (pinfunction "VCC_52") (pintype "power_in"))
      (node (ref "IC2") (pin "58") (pinfunction "VCC_58") (pintype "power_in"))
      (node (ref "IC2") (pin "63") (pinfunction "I2C_EN_63") (pintype "input"))
      (node (ref "IC2") (pin "64") (pinfunction "VCC_64") (pintype "power_in"))
      (node (ref "IC2") (pin "7") (pinfunction "VCC_7") (pintype "power_in"))
      (node (ref "IC3") (pin "13") (pinfunction "VCC_13") (pintype "power_in"))
      (node (ref "IC3") (pin "2") (pinfunction "VCC_2") (pintype "power_in"))
      (node (ref "IC3") (pin "20") (pinfunction "VCC_20") (pintype "power_in"))
      (node (ref "IC3") (pin "26") (pinfunction "VCC_26") (pintype "power_in"))
      (node (ref "IC3") (pin "30") (pinfunction "VCC_30") (pintype "power_in"))
      (node (ref "IC3") (pin "35") (pinfunction "VCC_35") (pintype "power_in"))
      (node (ref "IC3") (pin "41") (pinfunction "VCC_41") (pintype "power_in"))
      (node (ref "IC3") (pin "48") (pinfunction "ADDR2_48") (pintype "input"))
      (node (ref "IC3") (pin "52") (pinfunction "VCC_52") (pintype "power_in"))
      (node (ref "IC3") (pin "58") (pinfunction "VCC_58") (pintype "power_in"))
      (node (ref "IC3") (pin "63") (pinfunction "I2C_EN_63") (pintype "input"))
      (node (ref "IC3") (pin "64") (pinfunction "VCC_64") (pintype "power_in"))
      (node (ref "IC3") (pin "7") (pinfunction "VCC_7") (pintype "power_in"))
      (node (ref "R7") (pin "1") (pinfunction "1_1") (pintype "passive"))
      (node (ref "R8") (pin "1") (pinfunction "1_1") (pintype "passive"))
    )
    (net (code "2") (name "/A0_N") (class "Default")
      (node (ref "C38") (pin "1") (pinfunction "1_1") (pintype "passive"))
    )
    (net (code "3") (name "/A0_P") (class "Default")
      (node (ref "C37") (pin "1") (pinfunction "1_1") (pintype "passive"))
    )
    (net (code "4") (name "/A1_N") (class "Default")
      (node (ref "C40") (pin "1") (pinfunction "1_1") (pintype "passive"))
    )
    (net (code "5") (name "/A1_P") (class "Default")
      (node (ref "C39") (pin "1") (pinfunction "1_1") (pintype "passive"))
    )
    (net (code "6") (name "/A2_N") (class "Default")
      (node (ref "C42") (pin "1") (pinfunction "1_1") (pintype "passive"))
    )
    (net (code "7") (name "/A2_P") (class "Default")
      (node (ref "C41") (pin "1") (pinfunction "1_1") (pintype "passive"))
    )
    (net (code "8") (name "/A3_N") (class "Default")
      (node (ref "C44") (pin "1") (pinfunction "1_1") (pintype "passive"))
    )
    (net (code "9") (name "/A3_P") (class "Default")
      (node (ref "C43") (pin "1") (pinfunction "1_1") (pintype "passive"))
    )
    (net (code "10") (name "/A4_N") (class "Default")
      (node (ref "C47") (pin "1") (pinfunction "1_1") (pintype "passive"))
    )
    (net (code "11") (name "/A4_P") (class "Default")
      (node (ref "C45") (pin "1") (pinfunction "1_1") (pintype "passive"))
    )
    (net (code "12") (name "/A5_N") (class "Default")
      (node (ref "C51") (pin "1") (pinfunction "1_1") (pintype "passive"))
    )
    (net (code "13") (name "/A5_P") (class "Default")
      (node (ref "C49") (pin "1") (pinfunction "1_1") (pintype "passive"))
    )
    (net (code "14") (name "/A6_N") (class "Default")
      (node (ref "C54") (pin "1") (pinfunction "1_1") (pintype "passive"))
    )
    (net (code "15") (name "/A6_P") (class "Default")
      (node (ref "C53") (pin "1") (pinfunction "1_1") (pintype "passive"))
    )
    (net (code "16") (name "/A7_N") (class "Default")
      (node (ref "C60") (pin "1") (pinfunction "1_1") (pintype "passive"))
    )
    (net (code "17") (name "/A7_P") (class "Default")
      (node (ref "C58") (pin "1") (pinfunction "1_1") (pintype "passive"))
    )
    (net (code "18") (name "/A8_N") (class "Default")
      (node (ref "C62") (pin "1") (pinfunction "1_1") (pintype "passive"))
    )
    (net (code "19") (name "/A8_P") (class "Default")
      (node (ref "C61") (pin "1") (pinfunction "1_1") (pintype "passive"))
    )
    (net (code "20") (name "/A9_N") (class "Default")
      (node (ref "C64") (pin "1") (pinfunction "1_1") (pintype "passive"))
    )
    (net (code "21") (name "/A9_P") (class "Default")
      (node (ref "C63") (pin "1") (pinfunction "1_1") (pintype "passive"))
    )
    (net (code "22") (name "/A10_N") (class "Default")
      (node (ref "C66") (pin "1") (pinfunction "1_1") (pintype "passive"))
    )
    (net (code "23") (name "/A10_P") (class "Default")
      (node (ref "C65") (pin "1") (pinfunction "1_1") (pintype "passive"))
    )
    (net (code "24") (name "/A11_N") (class "Default")
      (node (ref "C68") (pin "1") (pinfunction "1_1") (pintype "passive"))
    )
    (net (code "25") (name "/A11_P") (class "Default")
      (node (ref "C67") (pin "1") (pinfunction "1_1") (pintype "passive"))
    )
    (net (code "26") (name "/A12_N") (class "Default")
      (node (ref "C70") (pin "1") (pinfunction "1_1") (pintype "passive"))
    )
    (net (code "27") (name "/A12_P") (class "Default")
      (node (ref "C69") (pin "1") (pinfunction "1_1") (pintype "passive"))
    )
    (net (code "28") (name "/A13_N") (class "Default")
      (node (ref "C72") (pin "1") (pinfunction "1_1") (pintype "passive"))
    )
    (net (code "29") (name "/A13_P") (class "Default")
      (node (ref "C71") (pin "1") (pinfunction "1_1") (pintype "passive"))
    )
    (net (code "30") (name "/B0_N") (class "Default")
      (node (ref "IC1") (pin "33") (pinfunction "OUT0_N_33") (pintype "output"))
    )
    (net (code "31") (name "/B0_P") (class "Default")
      (node (ref "IC1") (pin "34") (pinfunction "OUT0_P_34") (pintype "output"))
    )
    (net (code "32") (name "/B1_N") (class "Default")
      (node (ref "IC1") (pin "36") (pinfunction "OUT1_N_36") (pintype "output"))
    )
    (net (code "33") (name "/B1_P") (class "Default")
      (node (ref "IC1") (pin "37") (pinfunction "OUT1_P_37") (pintype "output"))
    )
    (net (code "34") (name "/B2_N") (class "Default")
      (node (ref "IC1") (pin "39") (pinfunction "OUT2_P_39") (pintype "output"))
    )
    (net (code "35") (name "/B2_P") (class "Default")
      (node (ref "IC1") (pin "40") (pinfunction "OUT2_N_40") (pintype "output"))
    )
    (net (code "36") (name "/B3_N") (class "Default")
      (node (ref "IC1") (pin "42") (pinfunction "OUT3_N_42") (pintype "output"))
    )
    (net (code "37") (name "/B3_P") (class "Default")
      (node (ref "IC1") (pin "43") (pinfunction "OUT3_P_43") (pintype "output"))
    )
    (net (code "38") (name "/B4_N") (class "Default")
      (node (ref "IC1") (pin "50") (pinfunction "OUT4_N_50") (pintype "output"))
    )
    (net (code "39") (name "/B4_P") (class "Default")
      (node (ref "IC1") (pin "51") (pinfunction "OUT4_P_51") (pintype "output"))
    )
    (net (code "40") (name "/B5_N") (class "Default")
      (node (ref "IC1") (pin "53") (pinfunction "OUT5_N_53") (pintype "output"))
    )
    (net (code "41") (name "/B5_P") (class "Default")
      (node (ref "IC1") (pin "54") (pinfunction "OUT5_P_54") (pintype "output"))
    )
    (net (code "42") (name "/B6_N") (class "Default")
      (node (ref "IC1") (pin "56") (pinfunction "OUT6_N_56") (pintype "output"))
    )
    (net (code "43") (name "/B6_P") (class "Default")
      (node (ref "IC1") (pin "57") (pinfunction "OUT6_P_57") (pintype "output"))
    )
    (net (code "44") (name "/B7_N") (class "Default")
      (node (ref "IC3") (pin "33") (pinfunction "OUT0_N_33") (pintype "output"))
    )
    (net (code "45") (name "/B7_P") (class "Default")
      (node (ref "IC3") (pin "34") (pinfunction "OUT0_P_34") (pintype "output"))
    )
    (net (code "46") (name "/B8_N") (class "Default")
      (node (ref "IC3") (pin "36") (pinfunction "OUT1_N_36") (pintype "output"))
    )
    (net (code "47") (name "/B8_P") (class "Default")
      (node (ref "IC3") (pin "37") (pinfunction "OUT1_P_37") (pintype "output"))
    )
    (net (code "48") (name "/B9_N") (class "Default")
      (node (ref "IC3") (pin "39") (pinfunction "OUT2_P_39") (pintype "output"))
    )
    (net (code "49") (name "/B9_P") (class "Default")
      (node (ref "IC3") (pin "40") (pinfunction "OUT2_N_40") (pintype "output"))
    )
    (net (code "50") (name "/B10_N") (class "Default")
      (node (ref "IC3") (pin "42") (pinfunction "OUT3_N_42") (pintype "output"))
    )
    (net (code "51") (name "/B10_P") (class "Default")
      (node (ref "IC3") (pin "43") (pinfunction "OUT3_P_43") (pintype "output"))
    )
    (net (code "52") (name "/B11_N") (class "Default")
      (node (ref "IC3") (pin "50") (pinfunction "OUT4_N_50") (pintype "output"))
    )
    (net (code "53") (name "/B11_P") (class "Default")
      (node (ref "IC3") (pin "51") (pinfunction "OUT4_P_51") (pintype "output"))
    )
    (net (code "54") (name "/B12_N") (class "Default")
      (node (ref "IC3") (pin "53") (pinfunction "OUT5_N_53") (pintype "output"))
    )
    (net (code "55") (name "/B12_P") (class "Default")
      (node (ref "IC3") (pin "54") (pinfunction "OUT5_P_54") (pintype "output"))
    )
    (net (code "56") (name "/B13_N") (class "Default")
      (node (ref "IC3") (pin "56") (pinfunction "OUT6_N_56") (pintype "output"))
    )
    (net (code "57") (name "/B13_P") (class "Default")
      (node (ref "IC3") (pin "57") (pinfunction "OUT6_P_57") (pintype "output"))
    )
    (net (code "58") (name "/FB_N") (class "Default")
      (node (ref "IC2") (pin "33") (pinfunction "OUT0_N_33") (pintype "output"))
    )
    (net (code "59") (name "/FB_P") (class "Default")
      (node (ref "IC2") (pin "34") (pinfunction "OUT0_P_34") (pintype "output"))
    )
    (net (code "60") (name "/NRST") (class "Default")
      (node (ref "IC1") (pin "3") (pinfunction "RESN_3") (pintype "input"))
      (node (ref "IC2") (pin "3") (pinfunction "RESN_3") (pintype "input"))
      (node (ref "IC3") (pin "3") (pinfunction "RESN_3") (pintype "input"))
    )
    (net (code "61") (name "/RX14_N") (class "Default")
      (node (ref "C56") (pin "1") (pinfunction "1_1") (pintype "passive"))
    )
    (net (code "62") (name "/RX14_P") (class "Default")
      (node (ref "C55") (pin "1") (pinfunction "1_1") (pintype "passive"))
    )
    (net (code "63") (name "/RX15_N") (class "Default")
      (node (ref "C59") (pin "1") (pinfunction "1_1") (pintype "passive"))
    )
    (net (code "64") (name "/RX15_P") (class "Default")
      (node (ref "C57") (pin "1") (pinfunction "1_1") (pintype "passive"))
    )
    (net (code "65") (name "/SCL") (class "Default")
      (node (ref "IC1") (pin "45") (pinfunction "SCL_45") (pintype "bidirectional"))
      (node (ref "IC2") (pin "45") (pinfunction "SCL_45") (pintype "bidirectional"))
      (node (ref "IC3") (pin "45") (pinfunction "SCL_45") (pintype "bidirectional"))
      (node (ref "R7") (pin "2") (pinfunction "2_2") (pintype "passive"))
    )
    (net (code "66") (name "/SDA") (class "Default")
      (node (ref "IC1") (pin "46") (pinfunction "SDA_46") (pintype "bidirectional"))
      (node (ref "IC2") (pin "46") (pinfunction "SDA_46") (pintype "bidirectional"))
      (node (ref "IC3") (pin "46") (pinfunction "SDA_46") (pintype "bidirectional"))
      (node (ref "R8") (pin "2") (pinfunction "2_2") (pintype "passive"))
    )
    (net (code "67") (name "/TX14_N") (class "Default")
      (node (ref "IC2") (pin "56") (pinfunction "OUT6_N_56") (pintype "output"))
    )
    (net (code "68") (name "/TX14_P") (class "Default")
      (node (ref "IC2") (pin "57") (pinfunction "OUT6_P_57") (pintype "output"))
    )
    (net (code "69") (name "/TX15_N") (class "Default")
      (node (ref "IC2") (pin "59") (pinfunction "OUT7_N_59") (pintype "output"))
    )
    (net (code "70") (name "/TX15_P") (class "Default")
      (node (ref "IC2") (pin "60") (pinfunction "OUT7_P_60") (pintype "output"))
    )
    (net (code "71") (name "GND") (class "Default")
      (node (ref "C1") (pin "1") (pinfunction "1_1") (pintype "passive"))
      (node (ref "C10") (pin "1") (pinfunction "1_1") (pintype "passive"))
      (node (ref "C11") (pin "1") (pinfunction "1_1") (pintype "passive"))
      (node (ref "C12") (pin "1") (pinfunction "1_1") (pintype "passive"))
      (node (ref "C13") (pin "1") (pinfunction "1_1") (pintype "passive"))
      (node (ref "C14") (pin "1") (pinfunction "1_1") (pintype "passive"))
      (node (ref "C15") (pin "1") (pinfunction "1_1") (pintype "passive"))
      (node (ref "C16") (pin "1") (pinfunction "1_1") (pintype "passive"))
      (node (ref "C17") (pin "1") (pinfunction "1_1") (pintype "passive"))
      (node (ref "C18") (pin "1") (pinfunction "1_1") (pintype "passive"))
      (node (ref "C19") (pin "1") (pinfunction "1_1") (pintype "passive"))
      (node (ref "C2") (pin "1") (pinfunction "1_1") (pintype "passive"))
      (node (ref "C20") (pin "1") (pinfunction "1_1") (pintype "passive"))
      (node (ref "C21") (pin "1") (pinfunction "1_1") (pintype "passive"))
      (node (ref "C22") (pin "1") (pinfunction "1_1") (pintype "passive"))
      (node (ref "C23") (pin "1") (pinfunction "1_1") (pintype "passive"))
      (node (ref "C24") (pin "1") (pinfunction "1_1") (pintype "passive"))
      (node (ref "C25") (pin "1") (pinfunction "1_1") (pintype "passive"))
      (node (ref "C26") (pin "1") (pinfunction "1_1") (pintype "passive"))
      (node (ref "C27") (pin "1") (pinfunction "1_1") (pintype "passive"))
      (node (ref "C28") (pin "1") (pinfunction "1_1") (pintype "passive"))
      (node (ref "C29") (pin "1") (pinfunction "1_1") (pintype "passive"))
      (node (ref "C3") (pin "1") (pinfunction "1_1") (pintype "passive"))
      (node (ref "C30") (pin "1") (pinfunction "1_1") (pintype "passive"))
      (node (ref "C31") (pin "1") (pinfunction "1_1") (pintype "passive"))
      (node (ref "C32") (pin "1") (pinfunction "1_1") (pintype "passive"))
      (node (ref "C33") (pin "1") (pinfunction "1_1") (pintype "passive"))
      (node (ref "C34") (pin "1") (pinfunction "1_1") (pintype "passive"))
      (node (ref "C35") (pin "1") (pinfunction "1_1") (pintype "passive"))
      (node (ref "C36") (pin "1") (pinfunction "1_1") (pintype "passive"))
      (node (ref "C4") (pin "1") (pinfunction "1_1") (pintype "passive"))
      (node (ref "C5") (pin "1") (pinfunction "1_1") (pintype "passive"))
      (node (ref "C6") (pin "1") (pinfunction "1_1") (pintype "passive"))
      (node (ref "C7") (pin "1") (pinfunction "1_1") (pintype "passive"))
      (node (ref "C8") (pin "1") (pinfunction "1_1") (pintype "passive"))
      (node (ref "C9") (pin "1") (pinfunction "1_1") (pintype "passive"))
      (node (ref "IC1") (pin "1") (pinfunction "GND_1") (pintype "power_in"))
      (node (ref "IC1") (pin "10") (pinfunction "GND_10") (pintype "power_in"))
      (node (ref "IC1") (pin "17") (pinfunction "GND_17") (pintype "power_in"))
      (node (ref "IC1") (pin "23") (pinfunction "GND_23") (pintype "power_in"))
      (node (ref "IC1") (pin "29") (pinfunction "GND_29") (pintype "power_in"))
      (node (ref "IC1") (pin "38") (pinfunction "GND_38") (pintype "power_in"))
      (node (ref "IC1") (pin "4") (pinfunction "GND_4") (pintype "power_in"))
      (node (ref "IC1") (pin "44") (pinfunction "GND_44") (pintype "power_in"))
      (node (ref "IC1") (pin "49") (pinfunction "GND_49") (pintype "power_in"))
      (node (ref "IC1") (pin "55") (pinfunction "GND_55") (pintype "power_in"))
      (node (ref "IC1") (pin "61") (pinfunction "GND_61") (pintype "power_in"))
      (node (ref "IC1") (pin "PAD") (pinfunction "PAD_GND_PAD") (pintype "power_in"))
      (node (ref "IC2") (pin "1") (pinfunction "GND_1") (pintype "power_in"))
      (node (ref "IC2") (pin "10") (pinfunction "GND_10") (pintype "power_in"))
      (node (ref "IC2") (pin "17") (pinfunction "GND_17") (pintype "power_in"))
      (node (ref "IC2") (pin "23") (pinfunction "GND_23") (pintype "power_in"))
      (node (ref "IC2") (pin "29") (pinfunction "GND_29") (pintype "power_in"))
      (node (ref "IC2") (pin "38") (pinfunction "GND_38") (pintype "power_in"))
      (node (ref "IC2") (pin "4") (pinfunction "GND_4") (pintype "power_in"))
      (node (ref "IC2") (pin "44") (pinfunction "GND_44") (pintype "power_in"))
      (node (ref "IC2") (pin "48") (pinfunction "ADDR2_48") (pintype "input"))
      (node (ref "IC2") (pin "49") (pinfunction "GND_49") (pintype "power_in"))
      (node (ref "IC2") (pin "55") (pinfunction "GND_55") (pintype "power_in"))
      (node (ref "IC2") (pin "61") (pinfunction "GND_61") (pintype "power_in"))
      (node (ref "IC2") (pin "PAD") (pinfunction "PAD_GND_PAD") (pintype "power_in"))
      (node (ref "IC3") (pin "1") (pinfunction "GND_1") (pintype "power_in"))
      (node (ref "IC3") (pin "10") (pinfunction "GND_10") (pintype "power_in"))
      (node (ref "IC3") (pin "17") (pinfunction "GND_17") (pintype "power_in"))
      (node (ref "IC3") (pin "23") (pinfunction "GND_23") (pintype "power_in"))
      (node (ref "IC3") (pin "29") (pinfunction "GND_29") (pintype "power_in"))
      (node (ref "IC3") (pin "38") (pinfunction "GND_38") (pintype "power_in"))
      (node (ref "IC3") (pin "4") (pinfunction "GND_4") (pintype "power_in"))
      (node (ref "IC3") (pin "44") (pinfunction "GND_44") (pintype "power_in"))
      (node (ref "IC3") (pin "47") (pinfunction "ADDR1_47") (pintype "input"))
      (node (ref "IC3") (pin "49") (pinfunction "GND_49") (pintype "power_in"))
      (node (ref "IC3") (pin "55") (pinfunction "GND_55") (pintype "power_in"))
      (node (ref "IC3") (pin "61") (pinfunction "GND_61") (pintype "power_in"))
      (node (ref "IC3") (pin "PAD") (pinfunction "PAD_GND_PAD") (pintype "power_in"))
    )
    (net (code "72") (name "Net-(IC1A-IN0_N)") (class "Default")
      (node (ref "C38") (pin "2") (pinfunction "2_2") (pintype "passive"))
      (node (ref "IC1") (pin "6") (pinfunction "IN0_N_6") (pintype "input"))
    )
    (net (code "73") (name "Net-(IC1A-IN0_P)") (class "Default")
      (node (ref "C37") (pin "2") (pinfunction "2_2") (pintype "passive"))
      (node (ref "IC1") (pin "5") (pinfunction "IN0_P_5") (pintype "input"))
    )
    (net (code "74") (name "Net-(IC1A-IN1_N)") (class "Default")
      (node (ref "C40") (pin "2") (pinfunction "2_2") (pintype "passive"))
      (node (ref "IC1") (pin "9") (pinfunction "IN1_N_9") (pintype "input"))
    )
    (net (code "75") (name "Net-(IC1A-IN1_P)") (class "Default")
      (node (ref "C39") (pin "2") (pinfunction "2_2") (pintype "passive"))
      (node (ref "IC1") (pin "8") (pinfunction "IN1_P_8") (pintype "input"))
    )
    (net (code "76") (name "Net-(IC1A-IN2_N)") (class "Default")
      (node (ref "C42") (pin "2") (pinfunction "2_2") (pintype "passive"))
      (node (ref "IC1") (pin "12") (pinfunction "IN2_N_12") (pintype "input"))
    )
    (net (code "77") (name "Net-(IC1A-IN2_P)") (class "Default")
      (node (ref "C41") (pin "2") (pinfunction "2_2") (pintype "passive"))
      (node (ref "IC1") (pin "11") (pinfunction "IN2_P_11") (pintype "input"))
    )
    (net (code "78") (name "Net-(IC1A-IN3_N)") (class "Default")
      (node (ref "C44") (pin "2") (pinfunction "2_2") (pintype "passive"))
      (node (ref "IC1") (pin "15") (pinfunction "IN3_N_15") (pintype "input"))
    )
    (net (code "79") (name "Net-(IC1A-IN3_P)") (class "Default")
      (node (ref "C43") (pin "2") (pinfunction "2_2") (pintype "passive"))
      (node (ref "IC1") (pin "14") (pinfunction "IN3_P_14") (pintype "input"))
    )
    (net (code "80") (name "Net-(IC1A-IN4_N)") (class "Default")
      (node (ref "C47") (pin "2") (pinfunction "2_2") (pintype "passive"))
      (node (ref "IC1") (pin "19") (pinfunction "IN4_N_19") (pintype "input"))
    )
    (net (code "81") (name "Net-(IC1A-IN4_P)") (class "Default")
      (node (ref "C45") (pin "2") (pinfunction "2_2") (pintype "passive"))
      (node (ref "IC1") (pin "18") (pinfunction "IN4_P_18") (pintype "input"))
    )
    (net (code "82") (name "Net-(IC1A-IN5_N)") (class "Default")
      (node (ref "C51") (pin "2") (pinfunction "2_2") (pintype "passive"))
      (node (ref "IC1") (pin "22") (pinfunction "IN5_N_22") (pintype "input"))
    )
    (net (code "83") (name "Net-(IC1A-IN5_P)") (class "Default")
      (node (ref "C49") (pin "2") (pinfunction "2_2") (pintype "passive"))
      (node (ref "IC1") (pin "21") (pinfunction "IN5_P_21") (pintype "input"))
    )
    (net (code "84") (name "Net-(IC1A-IN6_N)") (class "Default")
      (node (ref "C54") (pin "2") (pinfunction "2_2") (pintype "passive"))
      (node (ref "IC1") (pin "25") (pinfunction "IN6_N_25") (pintype "input"))
    )
    (net (code "85") (name "Net-(IC1A-IN6_P)") (class "Default")
      (node (ref "C53") (pin "2") (pinfunction "2_2") (pintype "passive"))
      (node (ref "IC1") (pin "24") (pinfunction "IN6_P_24") (pintype "input"))
    )
    (net (code "86") (name "Net-(IC1A-OUT7_N)") (class "Default")
      (node (ref "C83") (pin "1") (pinfunction "1_1") (pintype "passive"))
      (node (ref "IC1") (pin "59") (pinfunction "OUT7_N_59") (pintype "output"))
    )
    (net (code "87") (name "Net-(IC1A-OUT7_P)") (class "Default")
      (node (ref "C82") (pin "1") (pinfunction "1_1") (pintype "passive"))
      (node (ref "IC1") (pin "60") (pinfunction "OUT7_P_60") (pintype "output"))
    )
    (net (code "88") (name "Net-(IC2A-IN0_N)") (class "Default")
      (node (ref "C83") (pin "2") (pinfunction "2_2") (pintype "passive"))
      (node (ref "IC2") (pin "6") (pinfunction "IN0_N_6") (pintype "input"))
    )
    (net (code "89") (name "Net-(IC2A-IN0_P)") (class "Default")
      (node (ref "C82") (pin "2") (pinfunction "2_2") (pintype "passive"))
      (node (ref "IC2") (pin "5") (pinfunction "IN0_P_5") (pintype "input"))
    )
    (net (code "90") (name "Net-(IC2A-IN1_N)") (class "Default")
      (node (ref "C52") (pin "2") (pinfunction "2_2") (pintype "passive"))
      (node (ref "IC2") (pin "9") (pinfunction "IN1_N_9") (pintype "input"))
    )
    (net (code "91") (name "Net-(IC2A-IN1_P)") (class "Default")
      (node (ref "C50") (pin "2") (pinfunction "2_2") (pintype "passive"))
      (node (ref "IC2") (pin "8") (pinfunction "IN1_P_8") (pintype "input"))
    )
    (net (code "92") (name "Net-(IC2A-IN6_N)") (class "Default")
      (node (ref "C56") (pin "2") (pinfunction "2_2") (pintype "passive"))
      (node (ref "IC2") (pin "25") (pinfunction "IN6_N_25") (pintype "input"))
    )
    (net (code "93") (name "Net-(IC2A-IN6_P)") (class "Default")
      (node (ref "C55") (pin "2") (pinfunction "2_2") (pintype "passive"))
      (node (ref "IC2") (pin "24") (pinfunction "IN6_P_24") (pintype "input"))
    )
    (net (code "94") (name "Net-(IC2A-IN7_N)") (class "Default")
      (node (ref "C59") (pin "2") (pinfunction "2_2") (pintype "passive"))
      (node (ref "IC2") (pin "28") (pinfunction "IN7_N_28") (pintype "input"))
    )
    (net (code "95") (name "Net-(IC2A-IN7_P)") (class "Default")
      (node (ref "C57") (pin "2") (pinfunction "2_2") (pintype "passive"))
      (node (ref "IC2") (pin "27") (pinfunction "IN7_P_27") (pintype "input"))
    )
    (net (code "96") (name "Net-(IC2B-VBB)") (class "Default")
      (node (ref "C35") (pin "2") (pinfunction "2_2") (pintype "passive"))
      (node (ref "IC2") (pin "16") (pinfunction "VBB_16") (pintype "power_in"))
    )
    (net (code "97") (name "Net-(IC3A-IN0_N)") (class "Default")
      (node (ref "C60") (pin "2") (pinfunction "2_2") (pintype "passive"))
      (node (ref "IC3") (pin "6") (pinfunction "IN0_N_6") (pintype "input"))
    )
    (net (code "98") (name "Net-(IC3A-IN0_P)") (class "Default")
      (node (ref "C58") (pin "2") (pinfunction "2_2") (pintype "passive"))
      (node (ref "IC3") (pin "5") (pinfunction "IN0_P_5") (pintype "input"))
    )
    (net (code "99") (name "Net-(IC3A-IN1_N)") (class "Default")
      (node (ref "C62") (pin "2") (pinfunction "2_2") (pintype "passive"))
      (node (ref "IC3") (pin "9") (pinfunction "IN1_N_9") (pintype "input"))
    )
    (net (code "100") (name "Net-(IC3A-IN1_P)") (class "Default")
      (node (ref "C61") (pin "2") (pinfunction "2_2") (pintype "passive"))
      (node (ref "IC3") (pin "8") (pinfunction "IN1_P_8") (pintype "input"))
    )
    (net (code "101") (name "Net-(IC3A-IN2_N)") (class "Default")
      (node (ref "C64") (pin "2") (pinfunction "2_2") (pintype "passive"))
      (node (ref "IC3") (pin "12") (pinfunction "IN2_N_12") (pintype "input"))
    )
    (net (code "102") (name "Net-(IC3A-IN2_P)") (class "Default")
      (node (ref "C63") (pin "2") (pinfunction "2_2") (pintype "passive"))
      (node (ref "IC3") (pin "11") (pinfunction "IN2_P_11") (pintype "input"))
    )
    (net (code "103") (name "Net-(IC3A-IN3_N)") (class "Default")
      (node (ref "C66") (pin "2") (pinfunction "2_2") (pintype "passive"))
      (node (ref "IC3") (pin "15") (pinfunction "IN3_N_15") (pintype "input"))
    )
    (net (code "104") (name "Net-(IC3A-IN3_P)") (class "Default")
      (node (ref "C65") (pin "2") (pinfunction "2_2") (pintype "passive"))
      (node (ref "IC3") (pin "14") (pinfunction "IN3_P_14") (pintype "input"))
    )
    (net (code "105") (name "Net-(IC3A-IN4_N)") (class "Default")
      (node (ref "C68") (pin "2") (pinfunction "2_2") (pintype "passive"))
      (node (ref "IC3") (pin "19") (pinfunction "IN4_N_19") (pintype "input"))
    )
    (net (code "106") (name "Net-(IC3A-IN4_P)") (class "Default")
      (node (ref "C67") (pin "2") (pinfunction "2_2") (pintype "passive"))
      (node (ref "IC3") (pin "18") (pinfunction "IN4_P_18") (pintype "input"))
    )
    (net (code "107") (name "Net-(IC3A-IN5_N)") (class "Default")
      (node (ref "C70") (pin "2") (pinfunction "2_2") (pintype "passive"))
      (node (ref "IC3") (pin "22") (pinfunction "IN5_N_22") (pintype "input"))
    )
    (net (code "108") (name "Net-(IC3A-IN5_P)") (class "Default")
      (node (ref "C69") (pin "2") (pinfunction "2_2") (pintype "passive"))
      (node (ref "IC3") (pin "21") (pinfunction "IN5_P_21") (pintype "input"))
    )
    (net (code "109") (name "Net-(IC3A-IN6_N)") (class "Default")
      (node (ref "C72") (pin "2") (pinfunction "2_2") (pintype "passive"))
      (node (ref "IC3") (pin "25") (pinfunction "IN6_N_25") (pintype "input"))
    )
    (net (code "110") (name "Net-(IC3A-IN6_P)") (class "Default")
      (node (ref "C71") (pin "2") (pinfunction "2_2") (pintype "passive"))
      (node (ref "IC3") (pin "24") (pinfunction "IN6_P_24") (pintype "input"))
    )
    (net (code "111") (name "Net-(IC3A-OUT7_N)") (class "Default")
      (node (ref "C52") (pin "1") (pinfunction "1_1") (pintype "passive"))
      (node (ref "IC3") (pin "59") (pinfunction "OUT7_N_59") (pintype "output"))
    )
    (net (code "112") (name "Net-(IC3A-OUT7_P)") (class "Default")
      (node (ref "C50") (pin "1") (pinfunction "1_1") (pintype "passive"))
      (node (ref "IC3") (pin "60") (pinfunction "OUT7_P_60") (pintype "output"))
    )
    (net (code "113") (name "XPT_VBB") (class "Default")
      (node (ref "C34") (pin "2") (pinfunction "2_2") (pintype "passive"))
      (node (ref "C36") (pin "2") (pinfunction "2_2") (pintype "passive"))
      (node (ref "IC1") (pin "16") (pinfunction "VBB_16") (pintype "power_in"))
      (node (ref "IC3") (pin "16") (pinfunction "VBB_16") (pintype "power_in"))
    )
    (net (code "114") (name "unconnected-(IC1A-EQ-Pad31)") (class "Default")
      (node (ref "IC1") (pin "31") (pinfunction "EQ_31") (pintype "input"))
    )
    (net (code "115") (name "unconnected-(IC1A-IN7_N-Pad28)") (class "Default")
      (node (ref "IC1") (pin "28") (pinfunction "IN7_N_28") (pintype "input"))
    )
    (net (code "116") (name "unconnected-(IC1A-IN7_P-Pad27)") (class "Default")
      (node (ref "IC1") (pin "27") (pinfunction "IN7_P_27") (pintype "input"))
    )
    (net (code "117") (name "unconnected-(IC1A-PRE-Pad32)") (class "Default")
      (node (ref "IC1") (pin "32") (pinfunction "PRE_32") (pintype "input"))
    )
    (net (code "118") (name "unconnected-(IC1A-SWT-Pad62)") (class "Default")
      (node (ref "IC1") (pin "62") (pinfunction "SWT_62") (pintype "input"))
    )
    (net (code "119") (name "unconnected-(IC2A-EQ-Pad31)") (class "Default")
      (node (ref "IC2") (pin "31") (pinfunction "EQ_31") (pintype "input"))
    )
    (net (code "120") (name "unconnected-(IC2A-IN2_N-Pad12)") (class "Default")
      (node (ref "IC2") (pin "12") (pinfunction "IN2_N_12") (pintype "input"))
    )
    (net (code "121") (name "unconnected-(IC2A-IN2_P-Pad11)") (class "Default")
      (node (ref "IC2") (pin "11") (pinfunction "IN2_P_11") (pintype "input"))
    )
    (net (code "122") (name "unconnected-(IC2A-IN3_N-Pad15)") (class "Default")
      (node (ref "IC2") (pin "15") (pinfunction "IN3_N_15") (pintype "input"))
    )
    (net (code "123") (name "unconnected-(IC2A-IN3_P-Pad14)") (class "Default")
      (node (ref "IC2") (pin "14") (pinfunction "IN3_P_14") (pintype "input"))
    )
    (net (code "124") (name "unconnected-(IC2A-IN4_N-Pad19)") (class "Default")
      (node (ref "IC2") (pin "19") (pinfunction "IN4_N_19") (pintype "input"))
    )
    (net (code "125") (name "unconnected-(IC2A-IN4_P-Pad18)") (class "Default")
      (node (ref "IC2") (pin "18") (pinfunction "IN4_P_18") (pintype "input"))
    )
    (net (code "126") (name "unconnected-(IC2A-IN5_N-Pad22)") (class "Default")
      (node (ref "IC2") (pin "22") (pinfunction "IN5_N_22") (pintype "input"))
    )
    (net (code "127") (name "unconnected-(IC2A-IN5_P-Pad21)") (class "Default")
      (node (ref "IC2") (pin "21") (pinfunction "IN5_P_21") (pintype "input"))
    )
    (net (code "128") (name "unconnected-(IC2A-OUT1_N-Pad36)") (class "Default")
      (node (ref "IC2") (pin "36") (pinfunction "OUT1_N_36") (pintype "output"))
    )
    (net (code "129") (name "unconnected-(IC2A-OUT1_P-Pad37)") (class "Default")
      (node (ref "IC2") (pin "37") (pinfunction "OUT1_P_37") (pintype "output"))
    )
    (net (code "130") (name "unconnected-(IC2A-OUT2_N-Pad40)") (class "Default")
      (node (ref "IC2") (pin "40") (pinfunction "OUT2_N_40") (pintype "output"))
    )
    (net (code "131") (name "unconnected-(IC2A-OUT2_P-Pad39)") (class "Default")
      (node (ref "IC2") (pin "39") (pinfunction "OUT2_P_39") (pintype "output"))
    )
    (net (code "132") (name "unconnected-(IC2A-OUT3_N-Pad42)") (class "Default")
      (node (ref "IC2") (pin "42") (pinfunction "OUT3_N_42") (pintype "output"))
    )
    (net (code "133") (name "unconnected-(IC2A-OUT3_P-Pad43)") (class "Default")
      (node (ref "IC2") (pin "43") (pinfunction "OUT3_P_43") (pintype "output"))
    )
    (net (code "134") (name "unconnected-(IC2A-OUT4_N-Pad50)") (class "Default")
      (node (ref "IC2") (pin "50") (pinfunction "OUT4_N_50") (pintype "output"))
    )
    (net (code "135") (name "unconnected-(IC2A-OUT4_P-Pad51)") (class "Default")
      (node (ref "IC2") (pin "51") (pinfunction "OUT4_P_51") (pintype "output"))
    )
    (net (code "136") (name "unconnected-(IC2A-OUT5_N-Pad53)") (class "Default")
      (node (ref "IC2") (pin "53") (pinfunction "OUT5_N_53") (pintype "output"))
    )
    (net (code "137") (name "unconnected-(IC2A-OUT5_P-Pad54)") (class "Default")
      (node (ref "IC2") (pin "54") (pinfunction "OUT5_P_54") (pintype "output"))
    )
    (net (code "138") (name "unconnected-(IC2A-PRE-Pad32)") (class "Default")
      (node (ref "IC2") (pin "32") (pinfunction "PRE_32") (pintype "input"))
    )
    (net (code "139") (name "unconnected-(IC2A-SWT-Pad62)") (class "Default")
      (node (ref "IC2") (pin "62") (pinfunction "SWT_62") (pintype "input"))
    )
    (net (code "140") (name "unconnected-(IC3A-EQ-Pad31)") (class "Default")
      (node (ref "IC3") (pin "31") (pinfunction "EQ_31") (pintype "input"))
    )
    (net (code "141") (name "unconnected-(IC3A-IN7_N-Pad28)") (class "Default")
      (node (ref "IC3") (pin "28") (pinfunction "IN7_N_28") (pintype "input"))
    )
    (net (code "142") (name "unconnected-(IC3A-IN7_P-Pad27)") (class "Default")
      (node (ref "IC3") (pin "27") (pinfunction "IN7_P_27") (pintype "input"))
    )
    (net (code "143") (name "unconnected-(IC3A-PRE-Pad32)") (class "Default")
      (node (ref "IC3") (pin "32") (pinfunction "PRE_32") (pintype "input"))
    )
    (net (code "144") (name "unconnected-(IC3A-SWT-Pad62)") (class "Default")
      (node (ref "IC3") (pin "62") (pinfunction "SWT_62") (pintype "input"))
    )
  )
)
